# base_board4.net
KiCad netlist of a schematic drawn in EAGLE
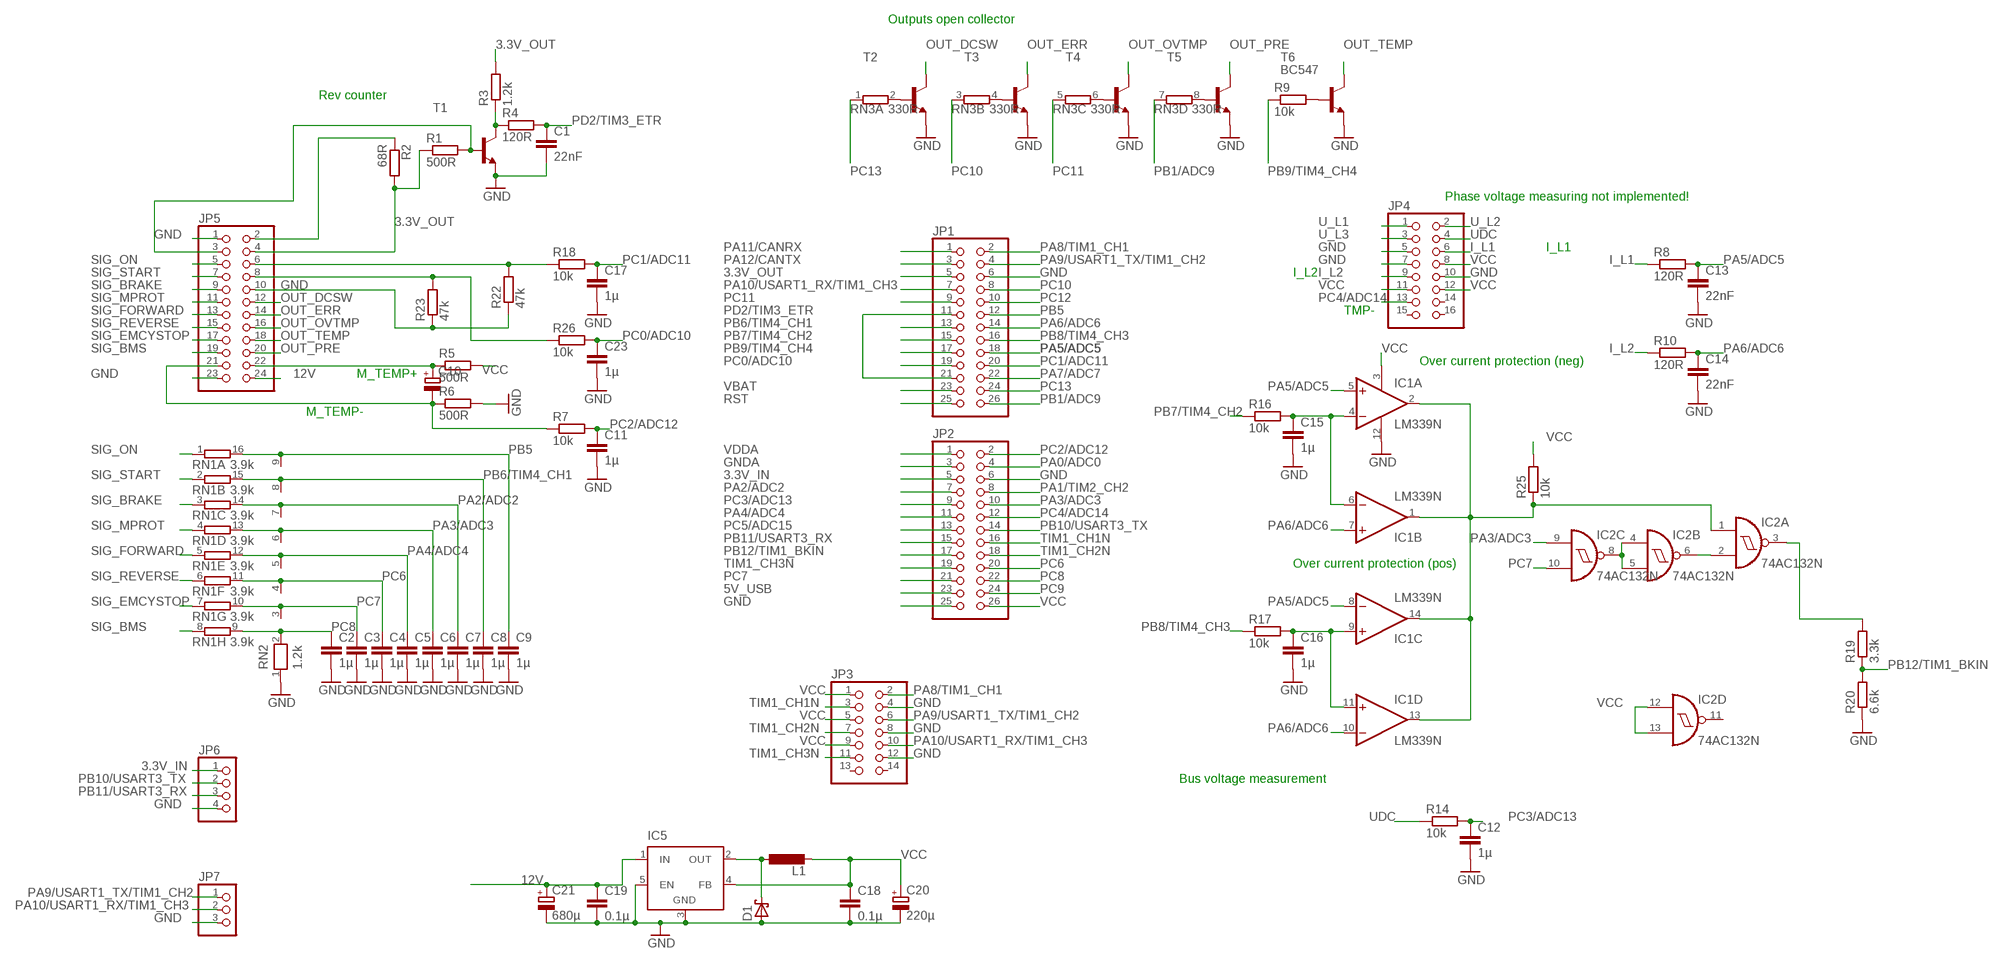
[diagram p0: schematic, sheet 1]

(export (version "E")
  (design (tool "Eeschema 10.0.6"))
  (components
    (comp (ref "C1")
      (value "22nF")
      (footprint "eagle-import:C025-024X044")
      (libsource (lib "eagle-import") (part "C-EU025-024X044"))
    )
    (comp (ref "C2")
      (value "1µ")
      (footprint "eagle-import:C025-024X044")
      (libsource (lib "eagle-import") (part "C-EU025-024X044"))
    )
    (comp (ref "C3")
      (value "1µ")
      (footprint "eagle-import:C025-024X044")
      (libsource (lib "eagle-import") (part "C-EU025-024X044"))
    )
    (comp (ref "C4")
      (value "1µ")
      (footprint "eagle-import:C025-024X044")
      (libsource (lib "eagle-import") (part "C-EU025-024X044"))
    )
    (comp (ref "C5")
      (value "1µ")
      (footprint "eagle-import:C025-024X044")
      (libsource (lib "eagle-import") (part "C-EU025-024X044"))
    )
    (comp (ref "C6")
      (value "1µ")
      (footprint "eagle-import:C025-024X044")
      (libsource (lib "eagle-import") (part "C-EU025-024X044"))
    )
    (comp (ref "C7")
      (value "1µ")
      (footprint "eagle-import:C025-024X044")
      (libsource (lib "eagle-import") (part "C-EU025-024X044"))
    )
    (comp (ref "C8")
      (value "1µ")
      (footprint "eagle-import:C025-024X044")
      (libsource (lib "eagle-import") (part "C-EU025-024X044"))
    )
    (comp (ref "C9")
      (value "1µ")
      (footprint "eagle-import:C025-024X044")
      (libsource (lib "eagle-import") (part "C-EU025-024X044"))
    )
    (comp (ref "C10")
      (value "CPOL-EUE2-4")
      (footprint "eagle-import:E2-4")
      (libsource (lib "eagle-import") (part "CPOL-EUE2-4"))
    )
    (comp (ref "C11")
      (value "1µ")
      (footprint "eagle-import:C025-024X044")
      (libsource (lib "eagle-import") (part "C-EU025-024X044"))
    )
    (comp (ref "C12")
      (value "1µ")
      (footprint "eagle-import:C025-024X044")
      (libsource (lib "eagle-import") (part "C-EU025-024X044"))
    )
    (comp (ref "C13")
      (value "22nF")
      (footprint "eagle-import:C025-024X044")
      (libsource (lib "eagle-import") (part "C-EU025-024X044"))
    )
    (comp (ref "C14")
      (value "22nF")
      (footprint "eagle-import:C025-024X044")
      (libsource (lib "eagle-import") (part "C-EU025-024X044"))
    )
    (comp (ref "C15")
      (value "1µ")
      (footprint "eagle-import:C025-024X044")
      (libsource (lib "eagle-import") (part "C-EU025-024X044"))
    )
    (comp (ref "C16")
      (value "1µ")
      (footprint "eagle-import:C025-024X044")
      (libsource (lib "eagle-import") (part "C-EU025-024X044"))
    )
    (comp (ref "C17")
      (value "1µ")
      (footprint "eagle-import:C025-024X044")
      (libsource (lib "eagle-import") (part "C-EU025-024X044"))
    )
    (comp (ref "C18")
      (value "0.1µ")
      (footprint "eagle-import:C050-024X044")
      (libsource (lib "eagle-import") (part "C-EU050-024X044"))
    )
    (comp (ref "C19")
      (value "0.1µ")
      (footprint "eagle-import:C050-024X044")
      (libsource (lib "eagle-import") (part "C-EU050-024X044"))
    )
    (comp (ref "C20")
      (value "220µ")
      (footprint "eagle-import:E2-4")
      (libsource (lib "eagle-import") (part "CPOL-EUE2-4"))
    )
    (comp (ref "C21")
      (value "680µ")
      (footprint "eagle-import:E2,5-5")
      (libsource (lib "eagle-import") (part "CPOL-EUE2.5-5"))
    )
    (comp (ref "C23")
      (value "1µ")
      (footprint "eagle-import:C025-024X044")
      (libsource (lib "eagle-import") (part "C-EU025-024X044"))
    )
    (comp (ref "D1")
      (value "SCHOTTKY-DIODEDO201T15")
      (footprint "eagle-import:DO201T15")
      (libsource (lib "eagle-import") (part "SCHOTTKY-DIODEDO201T15"))
    )
    (comp (ref "IC1")
      (value "LM339N")
      (footprint "eagle-import:DIL14")
      (libsource (lib "eagle-import") (part "LM339N"))
    )
    (comp (ref "IC2")
      (value "74AC132N")
      (footprint "eagle-import:DIL14")
      (libsource (lib "eagle-import") (part "74132NAC"))
    )
    (comp (ref "IC5")
      (value "LM2596TV")
      (footprint "eagle-import:TO220-51")
      (libsource (lib "eagle-import") (part "LM2596TV"))
    )
    (comp (ref "JP1")
      (value "PINHD-2X13")
      (footprint "eagle-import:2X13")
      (libsource (lib "eagle-import") (part "PINHD-2X13"))
    )
    (comp (ref "JP2")
      (value "PINHD-2X13")
      (footprint "eagle-import:2X13")
      (libsource (lib "eagle-import") (part "PINHD-2X13"))
    )
    (comp (ref "JP3")
      (value "PINHD-2X7")
      (footprint "eagle-import:2X07")
      (libsource (lib "eagle-import") (part "PINHD-2X7"))
    )
    (comp (ref "JP4")
      (value "PINHD-2X8")
      (footprint "eagle-import:2X08")
      (libsource (lib "eagle-import") (part "PINHD-2X8"))
    )
    (comp (ref "JP5")
      (value "PINHD-2X12")
      (footprint "eagle-import:2X12")
      (libsource (lib "eagle-import") (part "PINHD-2X12"))
    )
    (comp (ref "JP6")
      (value "PINHD-1X4")
      (footprint "eagle-import:1X04")
      (libsource (lib "eagle-import") (part "PINHD-1X4"))
    )
    (comp (ref "JP7")
      (value "PINHD-1X3")
      (footprint "eagle-import:1X03")
      (libsource (lib "eagle-import") (part "PINHD-1X3"))
    )
    (comp (ref "L1")
      (value "L-EUTJ3-U1")
      (footprint "eagle-import:TJ3-U1")
      (libsource (lib "eagle-import") (part "L-EUTJ3-U1"))
    )
    (comp (ref "R1")
      (value "500R")
      (footprint "eagle-import:0207_10")
      (libsource (lib "eagle-import") (part "R-EU_0207/10"))
    )
    (comp (ref "R2")
      (value "68R")
      (footprint "eagle-import:0207_10")
      (libsource (lib "eagle-import") (part "R-EU_0207/10"))
    )
    (comp (ref "R3")
      (value "1.2k")
      (footprint "eagle-import:0207_10")
      (libsource (lib "eagle-import") (part "R-EU_0207/10"))
    )
    (comp (ref "R4")
      (value "120R")
      (footprint "eagle-import:0207_10")
      (libsource (lib "eagle-import") (part "R-EU_0207/10"))
    )
    (comp (ref "R5")
      (value "500R")
      (footprint "eagle-import:0207_10")
      (libsource (lib "eagle-import") (part "R-EU_0207/10"))
    )
    (comp (ref "R6")
      (value "500R")
      (footprint "eagle-import:0207_10")
      (libsource (lib "eagle-import") (part "R-EU_0207/10"))
    )
    (comp (ref "R7")
      (value "10k")
      (footprint "eagle-import:0207_10")
      (libsource (lib "eagle-import") (part "R-EU_0207/10"))
    )
    (comp (ref "R8")
      (value "120R")
      (footprint "eagle-import:0207_10")
      (libsource (lib "eagle-import") (part "R-EU_0207/10"))
    )
    (comp (ref "R9")
      (value "10k")
      (footprint "eagle-import:0207_10")
      (libsource (lib "eagle-import") (part "R-EU_0207/10"))
    )
    (comp (ref "R10")
      (value "120R")
      (footprint "eagle-import:0207_10")
      (libsource (lib "eagle-import") (part "R-EU_0207/10"))
    )
    (comp (ref "R14")
      (value "10k")
      (footprint "eagle-import:0207_10")
      (libsource (lib "eagle-import") (part "R-EU_0207/10"))
    )
    (comp (ref "R16")
      (value "10k")
      (footprint "eagle-import:0207_10")
      (libsource (lib "eagle-import") (part "R-EU_0207/10"))
    )
    (comp (ref "R17")
      (value "10k")
      (footprint "eagle-import:0207_10")
      (libsource (lib "eagle-import") (part "R-EU_0207/10"))
    )
    (comp (ref "R18")
      (value "10k")
      (footprint "eagle-import:0207_10")
      (libsource (lib "eagle-import") (part "R-EU_0207/10"))
    )
    (comp (ref "R19")
      (value "3.3k")
      (footprint "eagle-import:0207_10")
      (libsource (lib "eagle-import") (part "R-EU_0207/10"))
    )
    (comp (ref "R20")
      (value "6.6k")
      (footprint "eagle-import:0207_10")
      (libsource (lib "eagle-import") (part "R-EU_0207/10"))
    )
    (comp (ref "R22")
      (value "47k")
      (footprint "eagle-import:0207_10")
      (libsource (lib "eagle-import") (part "R-EU_0207/10"))
    )
    (comp (ref "R23")
      (value "47k")
      (footprint "eagle-import:0207_10")
      (libsource (lib "eagle-import") (part "R-EU_0207/10"))
    )
    (comp (ref "R25")
      (value "10k")
      (footprint "eagle-import:0207_10")
      (libsource (lib "eagle-import") (part "R-EU_0207/10"))
    )
    (comp (ref "R26")
      (value "10k")
      (footprint "eagle-import:0207_10")
      (libsource (lib "eagle-import") (part "R-EU_0207/10"))
    )
    (comp (ref "RN1")
      (value "3.9k")
      (footprint "eagle-import:DIL16")
      (libsource (lib "eagle-import") (part "8R-N"))
    )
    (comp (ref "RN2")
      (value "1.2k")
      (footprint "eagle-import:RN-9")
      (libsource (lib "eagle-import") (part "RN08"))
    )
    (comp (ref "RN3")
      (value "330R")
      (footprint "eagle-import:SIL8")
      (libsource (lib "eagle-import") (part "E4R"))
    )
    (comp (ref "T1")
      (value "BC547B-NPN-TO92-EBC")
      (footprint "eagle-import:TO92-EBC")
      (libsource (lib "eagle-import") (part "-NPN-TO92-EBCBC547B"))
    )
    (comp (ref "T2")
      (value "-NPN-TO92-EBC")
      (footprint "eagle-import:TO92-EBC")
      (libsource (lib "eagle-import") (part "transistor-neu-to92_-NPN-TO92-EBC"))
    )
    (comp (ref "T3")
      (value "-NPN-TO92-EBC")
      (footprint "eagle-import:TO92-EBC")
      (libsource (lib "eagle-import") (part "transistor-neu-to92_-NPN-TO92-EBC"))
    )
    (comp (ref "T4")
      (value "-NPN-TO92-EBC")
      (footprint "eagle-import:TO92-EBC")
      (libsource (lib "eagle-import") (part "transistor-neu-to92_-NPN-TO92-EBC"))
    )
    (comp (ref "T5")
      (value "-NPN-TO92-EBC")
      (footprint "eagle-import:TO92-EBC")
      (libsource (lib "eagle-import") (part "transistor-neu-to92_-NPN-TO92-EBC"))
    )
    (comp (ref "T6")
      (value "BC547")
      (footprint "eagle-import:TO92")
      (libsource (lib "eagle-import") (part "BC547"))
    )
  )
  (nets
    (net (code "1") (name "/3.3V_IN") (class "Default")
      (node (ref "JP2") (pin "5") (pinfunction "5_5") (pintype "passive"))
      (node (ref "JP6") (pin "1") (pinfunction "1_1") (pintype "passive"))
    )
    (net (code "2") (name "/3.3V_OUT") (class "Default")
      (node (ref "JP1") (pin "5") (pinfunction "5_5") (pintype "passive"))
      (node (ref "JP5") (pin "4") (pinfunction "4_4") (pintype "passive"))
      (node (ref "R1") (pin "1") (pinfunction "1_1") (pintype "passive"))
      (node (ref "R2") (pin "2") (pinfunction "2_2") (pintype "passive"))
      (node (ref "R3") (pin "2") (pinfunction "2_2") (pintype "passive"))
    )
    (net (code "3") (name "/5V_USB") (class "Default")
      (node (ref "JP2") (pin "23") (pinfunction "23_23") (pintype "passive"))
    )
    (net (code "4") (name "/12V") (class "Default")
      (node (ref "C19") (pin "1") (pinfunction "1_1") (pintype "passive"))
      (node (ref "C21") (pin "+") (pinfunction "+_+") (pintype "passive"))
      (node (ref "IC5") (pin "1") (pinfunction "IN_1") (pintype "input"))
      (node (ref "JP5") (pin "24") (pinfunction "24_24") (pintype "passive"))
    )
    (net (code "5") (name "/GNDA") (class "Default")
      (node (ref "JP2") (pin "3") (pinfunction "3_3") (pintype "passive"))
    )
    (net (code "6") (name "/I_L1") (class "Default")
      (node (ref "JP4") (pin "6") (pinfunction "6_6") (pintype "passive"))
      (node (ref "R8") (pin "1") (pinfunction "1_1") (pintype "passive"))
    )
    (net (code "7") (name "/I_L2") (class "Default")
      (node (ref "JP4") (pin "9") (pinfunction "9_9") (pintype "passive"))
      (node (ref "R10") (pin "1") (pinfunction "1_1") (pintype "passive"))
    )
    (net (code "8") (name "/OUT_DCSW") (class "Default")
      (node (ref "JP5") (pin "12") (pinfunction "12_12") (pintype "passive"))
      (node (ref "T2") (pin "C") (pinfunction "C_C") (pintype "passive"))
    )
    (net (code "9") (name "/OUT_ERR") (class "Default")
      (node (ref "JP5") (pin "14") (pinfunction "14_14") (pintype "passive"))
      (node (ref "T3") (pin "C") (pinfunction "C_C") (pintype "passive"))
    )
    (net (code "10") (name "/OUT_OVTMP") (class "Default")
      (node (ref "JP5") (pin "16") (pinfunction "16_16") (pintype "passive"))
      (node (ref "T4") (pin "C") (pinfunction "C_C") (pintype "passive"))
    )
    (net (code "11") (name "/OUT_PRE") (class "Default")
      (node (ref "JP5") (pin "20") (pinfunction "20_20") (pintype "passive"))
      (node (ref "T5") (pin "C") (pinfunction "C_C") (pintype "passive"))
    )
    (net (code "12") (name "/OUT_TEMP") (class "Default")
      (node (ref "JP5") (pin "18") (pinfunction "18_18") (pintype "passive"))
      (node (ref "T6") (pin "3") (pinfunction "C_3") (pintype "passive"))
    )
    (net (code "13") (name "/PA0{slash}ADC0") (class "Default")
      (node (ref "JP2") (pin "4") (pinfunction "4_4") (pintype "passive"))
    )
    (net (code "14") (name "/PA1{slash}TIM2_CH2") (class "Default")
      (node (ref "JP2") (pin "8") (pinfunction "8_8") (pintype "passive"))
    )
    (net (code "15") (name "/PA2{slash}ADC2") (class "Default")
      (node (ref "C7") (pin "1") (pinfunction "1_1") (pintype "passive"))
      (node (ref "JP2") (pin "7") (pinfunction "7_7") (pintype "passive"))
      (node (ref "RN1") (pin "14") (pinfunction "2_14") (pintype "passive"))
      (node (ref "RN2") (pin "7") (pinfunction "7_7") (pintype "passive"))
    )
    (net (code "16") (name "/PA3{slash}ADC3") (class "Default")
      (node (ref "C6") (pin "1") (pinfunction "1_1") (pintype "passive"))
      (node (ref "IC2") (pin "9") (pinfunction "I0_9") (pintype "input"))
      (node (ref "JP2") (pin "10") (pinfunction "10_10") (pintype "passive"))
      (node (ref "RN1") (pin "13") (pinfunction "2_13") (pintype "passive"))
      (node (ref "RN2") (pin "6") (pinfunction "6_6") (pintype "passive"))
    )
    (net (code "17") (name "/PA4{slash}ADC4") (class "Default")
      (node (ref "C5") (pin "1") (pinfunction "1_1") (pintype "passive"))
      (node (ref "JP2") (pin "11") (pinfunction "11_11") (pintype "passive"))
      (node (ref "RN1") (pin "12") (pinfunction "2_12") (pintype "passive"))
      (node (ref "RN2") (pin "5") (pinfunction "5_5") (pintype "passive"))
    )
    (net (code "18") (name "/PA5{slash}ADC5") (class "Default")
      (node (ref "C13") (pin "1") (pinfunction "1_1") (pintype "passive"))
      (node (ref "IC1") (pin "5") (pinfunction "+IN_5") (pintype "input"))
      (node (ref "IC1") (pin "8") (pinfunction "-IN_8") (pintype "input"))
      (node (ref "JP1") (pin "18") (pinfunction "18_18") (pintype "passive"))
      (node (ref "R8") (pin "2") (pinfunction "2_2") (pintype "passive"))
    )
    (net (code "19") (name "/PA6{slash}ADC6") (class "Default")
      (node (ref "C14") (pin "1") (pinfunction "1_1") (pintype "passive"))
      (node (ref "IC1") (pin "10") (pinfunction "-IN_10") (pintype "input"))
      (node (ref "IC1") (pin "7") (pinfunction "+IN_7") (pintype "input"))
      (node (ref "JP1") (pin "14") (pinfunction "14_14") (pintype "passive"))
      (node (ref "R10") (pin "2") (pinfunction "2_2") (pintype "passive"))
    )
    (net (code "20") (name "/PA7{slash}ADC7") (class "Default")
      (node (ref "JP1") (pin "22") (pinfunction "22_22") (pintype "passive"))
    )
    (net (code "21") (name "/PA8{slash}TIM1_CH1") (class "Default")
      (node (ref "JP1") (pin "2") (pinfunction "2_2") (pintype "passive"))
      (node (ref "JP3") (pin "2") (pinfunction "2_2") (pintype "passive"))
    )
    (net (code "22") (name "/PA9{slash}USART1_TX{slash}TIM1_CH2") (class "Default")
      (node (ref "JP1") (pin "4") (pinfunction "4_4") (pintype "passive"))
      (node (ref "JP3") (pin "6") (pinfunction "6_6") (pintype "passive"))
      (node (ref "JP7") (pin "1") (pinfunction "1_1") (pintype "passive"))
    )
    (net (code "23") (name "/PA10{slash}USART1_RX{slash}TIM1_CH3") (class "Default")
      (node (ref "JP1") (pin "7") (pinfunction "7_7") (pintype "passive"))
      (node (ref "JP3") (pin "10") (pinfunction "10_10") (pintype "passive"))
      (node (ref "JP7") (pin "2") (pinfunction "2_2") (pintype "passive"))
    )
    (net (code "24") (name "/PA11{slash}CANRX") (class "Default")
      (node (ref "JP1") (pin "1") (pinfunction "1_1") (pintype "passive"))
    )
    (net (code "25") (name "/PA12{slash}CANTX") (class "Default")
      (node (ref "JP1") (pin "3") (pinfunction "3_3") (pintype "passive"))
    )
    (net (code "26") (name "/PB1{slash}ADC9") (class "Default")
      (node (ref "JP1") (pin "26") (pinfunction "26_26") (pintype "passive"))
      (node (ref "RN3") (pin "7") (pinfunction "1_7") (pintype "passive"))
    )
    (net (code "27") (name "/PB5") (class "Default")
      (node (ref "C9") (pin "1") (pinfunction "1_1") (pintype "passive"))
      (node (ref "JP1") (pin "12") (pinfunction "12_12") (pintype "passive"))
      (node (ref "RN1") (pin "16") (pinfunction "2_16") (pintype "passive"))
      (node (ref "RN2") (pin "9") (pinfunction "9_9") (pintype "passive"))
    )
    (net (code "28") (name "/PB6{slash}TIM4_CH1") (class "Default")
      (node (ref "C8") (pin "1") (pinfunction "1_1") (pintype "passive"))
      (node (ref "JP1") (pin "13") (pinfunction "13_13") (pintype "passive"))
      (node (ref "RN1") (pin "15") (pinfunction "2_15") (pintype "passive"))
      (node (ref "RN2") (pin "8") (pinfunction "8_8") (pintype "passive"))
    )
    (net (code "29") (name "/PB7{slash}TIM4_CH2") (class "Default")
      (node (ref "JP1") (pin "15") (pinfunction "15_15") (pintype "passive"))
      (node (ref "R16") (pin "1") (pinfunction "1_1") (pintype "passive"))
    )
    (net (code "30") (name "/PB8{slash}TIM4_CH3") (class "Default")
      (node (ref "JP1") (pin "16") (pinfunction "16_16") (pintype "passive"))
      (node (ref "R17") (pin "1") (pinfunction "1_1") (pintype "passive"))
    )
    (net (code "31") (name "/PB9{slash}TIM4_CH4") (class "Default")
      (node (ref "JP1") (pin "17") (pinfunction "17_17") (pintype "passive"))
      (node (ref "R9") (pin "1") (pinfunction "1_1") (pintype "passive"))
    )
    (net (code "32") (name "/PB10{slash}USART3_TX") (class "Default")
      (node (ref "JP2") (pin "14") (pinfunction "14_14") (pintype "passive"))
      (node (ref "JP6") (pin "2") (pinfunction "2_2") (pintype "passive"))
    )
    (net (code "33") (name "/PB11{slash}USART3_RX") (class "Default")
      (node (ref "JP2") (pin "15") (pinfunction "15_15") (pintype "passive"))
      (node (ref "JP6") (pin "3") (pinfunction "3_3") (pintype "passive"))
    )
    (net (code "34") (name "/PB12{slash}TIM1_BKIN") (class "Default")
      (node (ref "JP2") (pin "17") (pinfunction "17_17") (pintype "passive"))
      (node (ref "R19") (pin "1") (pinfunction "1_1") (pintype "passive"))
      (node (ref "R20") (pin "2") (pinfunction "2_2") (pintype "passive"))
    )
    (net (code "35") (name "/PC0{slash}ADC10") (class "Default")
      (node (ref "C23") (pin "1") (pinfunction "1_1") (pintype "passive"))
      (node (ref "JP1") (pin "19") (pinfunction "19_19") (pintype "passive"))
      (node (ref "R26") (pin "2") (pinfunction "2_2") (pintype "passive"))
    )
    (net (code "36") (name "/PC1{slash}ADC11") (class "Default")
      (node (ref "C17") (pin "1") (pinfunction "1_1") (pintype "passive"))
      (node (ref "JP1") (pin "20") (pinfunction "20_20") (pintype "passive"))
      (node (ref "R18") (pin "2") (pinfunction "2_2") (pintype "passive"))
    )
    (net (code "37") (name "/PC2{slash}ADC12") (class "Default")
      (node (ref "C11") (pin "1") (pinfunction "1_1") (pintype "passive"))
      (node (ref "JP2") (pin "2") (pinfunction "2_2") (pintype "passive"))
      (node (ref "R7") (pin "2") (pinfunction "2_2") (pintype "passive"))
    )
    (net (code "38") (name "/PC3{slash}ADC13") (class "Default")
      (node (ref "C12") (pin "1") (pinfunction "1_1") (pintype "passive"))
      (node (ref "JP2") (pin "9") (pinfunction "9_9") (pintype "passive"))
      (node (ref "R14") (pin "2") (pinfunction "2_2") (pintype "passive"))
    )
    (net (code "39") (name "/PC4{slash}ADC14") (class "Default")
      (node (ref "JP2") (pin "12") (pinfunction "12_12") (pintype "passive"))
      (node (ref "JP4") (pin "13") (pinfunction "13_13") (pintype "passive"))
    )
    (net (code "40") (name "/PC5{slash}ADC15") (class "Default")
      (node (ref "JP2") (pin "13") (pinfunction "13_13") (pintype "passive"))
    )
    (net (code "41") (name "/PC6") (class "Default")
      (node (ref "C4") (pin "1") (pinfunction "1_1") (pintype "passive"))
      (node (ref "JP2") (pin "20") (pinfunction "20_20") (pintype "passive"))
      (node (ref "RN1") (pin "11") (pinfunction "2_11") (pintype "passive"))
      (node (ref "RN2") (pin "4") (pinfunction "4_4") (pintype "passive"))
    )
    (net (code "42") (name "/PC7") (class "Default")
      (node (ref "C3") (pin "1") (pinfunction "1_1") (pintype "passive"))
      (node (ref "IC2") (pin "10") (pinfunction "I1_10") (pintype "input"))
      (node (ref "JP2") (pin "21") (pinfunction "21_21") (pintype "passive"))
      (node (ref "RN1") (pin "10") (pinfunction "2_10") (pintype "passive"))
      (node (ref "RN2") (pin "3") (pinfunction "3_3") (pintype "passive"))
    )
    (net (code "43") (name "/PC8") (class "Default")
      (node (ref "C2") (pin "1") (pinfunction "1_1") (pintype "passive"))
      (node (ref "JP2") (pin "22") (pinfunction "22_22") (pintype "passive"))
      (node (ref "RN1") (pin "9") (pinfunction "2_9") (pintype "passive"))
      (node (ref "RN2") (pin "2") (pinfunction "2_2") (pintype "passive"))
    )
    (net (code "44") (name "/PC9") (class "Default")
      (node (ref "JP2") (pin "24") (pinfunction "24_24") (pintype "passive"))
    )
    (net (code "45") (name "/PC10") (class "Default")
      (node (ref "JP1") (pin "8") (pinfunction "8_8") (pintype "passive"))
      (node (ref "RN3") (pin "3") (pinfunction "1_3") (pintype "passive"))
    )
    (net (code "46") (name "/PC11") (class "Default")
      (node (ref "JP1") (pin "9") (pinfunction "9_9") (pintype "passive"))
      (node (ref "RN3") (pin "5") (pinfunction "1_5") (pintype "passive"))
    )
    (net (code "47") (name "/PC12") (class "Default")
      (node (ref "JP1") (pin "10") (pinfunction "10_10") (pintype "passive"))
    )
    (net (code "48") (name "/PC13") (class "Default")
      (node (ref "JP1") (pin "24") (pinfunction "24_24") (pintype "passive"))
      (node (ref "RN3") (pin "1") (pinfunction "1_1") (pintype "passive"))
    )
    (net (code "49") (name "/PD2{slash}TIM3_ETR") (class "Default")
      (node (ref "C1") (pin "1") (pinfunction "1_1") (pintype "passive"))
      (node (ref "JP1") (pin "11") (pinfunction "11_11") (pintype "passive"))
      (node (ref "JP1") (pin "21") (pinfunction "21_21") (pintype "passive"))
      (node (ref "R4") (pin "2") (pinfunction "2_2") (pintype "passive"))
    )
    (net (code "50") (name "/RST") (class "Default")
      (node (ref "JP1") (pin "25") (pinfunction "25_25") (pintype "passive"))
    )
    (net (code "51") (name "/SIG_BMS") (class "Default")
      (node (ref "JP5") (pin "19") (pinfunction "19_19") (pintype "passive"))
      (node (ref "RN1") (pin "8") (pinfunction "1_8") (pintype "passive"))
    )
    (net (code "52") (name "/SIG_BRAKE") (class "Default")
      (node (ref "JP5") (pin "9") (pinfunction "9_9") (pintype "passive"))
      (node (ref "RN1") (pin "3") (pinfunction "1_3") (pintype "passive"))
    )
    (net (code "53") (name "/SIG_EMCYSTOP") (class "Default")
      (node (ref "JP5") (pin "17") (pinfunction "17_17") (pintype "passive"))
      (node (ref "RN1") (pin "7") (pinfunction "1_7") (pintype "passive"))
    )
    (net (code "54") (name "/SIG_FORWARD") (class "Default")
      (node (ref "JP5") (pin "13") (pinfunction "13_13") (pintype "passive"))
      (node (ref "RN1") (pin "5") (pinfunction "1_5") (pintype "passive"))
    )
    (net (code "55") (name "/SIG_MPROT") (class "Default")
      (node (ref "JP5") (pin "11") (pinfunction "11_11") (pintype "passive"))
      (node (ref "RN1") (pin "4") (pinfunction "1_4") (pintype "passive"))
    )
    (net (code "56") (name "/SIG_ON") (class "Default")
      (node (ref "JP5") (pin "5") (pinfunction "5_5") (pintype "passive"))
      (node (ref "RN1") (pin "1") (pinfunction "1_1") (pintype "passive"))
    )
    (net (code "57") (name "/SIG_REVERSE") (class "Default")
      (node (ref "JP5") (pin "15") (pinfunction "15_15") (pintype "passive"))
      (node (ref "RN1") (pin "6") (pinfunction "1_6") (pintype "passive"))
    )
    (net (code "58") (name "/SIG_START") (class "Default")
      (node (ref "JP5") (pin "7") (pinfunction "7_7") (pintype "passive"))
      (node (ref "RN1") (pin "2") (pinfunction "1_2") (pintype "passive"))
    )
    (net (code "59") (name "/TIM1_CH1N") (class "Default")
      (node (ref "JP2") (pin "16") (pinfunction "16_16") (pintype "passive"))
      (node (ref "JP3") (pin "3") (pinfunction "3_3") (pintype "passive"))
    )
    (net (code "60") (name "/TIM1_CH2N") (class "Default")
      (node (ref "JP2") (pin "18") (pinfunction "18_18") (pintype "passive"))
      (node (ref "JP3") (pin "7") (pinfunction "7_7") (pintype "passive"))
    )
    (net (code "61") (name "/TIM1_CH3N") (class "Default")
      (node (ref "JP2") (pin "19") (pinfunction "19_19") (pintype "passive"))
      (node (ref "JP3") (pin "11") (pinfunction "11_11") (pintype "passive"))
    )
    (net (code "62") (name "/UDC") (class "Default")
      (node (ref "JP4") (pin "4") (pinfunction "4_4") (pintype "passive"))
      (node (ref "R14") (pin "1") (pinfunction "1_1") (pintype "passive"))
    )
    (net (code "63") (name "/U_L1") (class "Default")
      (node (ref "JP4") (pin "1") (pinfunction "1_1") (pintype "passive"))
    )
    (net (code "64") (name "/U_L2") (class "Default")
      (node (ref "JP4") (pin "2") (pinfunction "2_2") (pintype "passive"))
    )
    (net (code "65") (name "/U_L3") (class "Default")
      (node (ref "JP4") (pin "3") (pinfunction "3_3") (pintype "passive"))
    )
    (net (code "66") (name "/VBAT") (class "Default")
      (node (ref "JP1") (pin "23") (pinfunction "23_23") (pintype "passive"))
    )
    (net (code "67") (name "/VCC") (class "Default")
      (node (ref "C18") (pin "1") (pinfunction "1_1") (pintype "passive"))
      (node (ref "C20") (pin "+") (pinfunction "+_+") (pintype "passive"))
      (node (ref "IC1") (pin "3") (pinfunction "V+_3") (pintype "power_in"))
      (node (ref "IC2") (pin "12") (pinfunction "I0_12") (pintype "input"))
      (node (ref "IC2") (pin "13") (pinfunction "I1_13") (pintype "input"))
      (node (ref "IC5") (pin "4") (pinfunction "FB_4") (pintype "input"))
      (node (ref "JP2") (pin "26") (pinfunction "26_26") (pintype "passive"))
      (node (ref "JP3") (pin "1") (pinfunction "1_1") (pintype "passive"))
      (node (ref "JP3") (pin "5") (pinfunction "5_5") (pintype "passive"))
      (node (ref "JP3") (pin "9") (pinfunction "9_9") (pintype "passive"))
      (node (ref "JP4") (pin "11") (pinfunction "11_11") (pintype "passive"))
      (node (ref "JP4") (pin "12") (pinfunction "12_12") (pintype "passive"))
      (node (ref "JP4") (pin "8") (pinfunction "8_8") (pintype "passive"))
      (node (ref "L1") (pin "2") (pinfunction "2_2") (pintype "passive"))
      (node (ref "R25") (pin "2") (pinfunction "2_2") (pintype "passive"))
      (node (ref "R5") (pin "2") (pinfunction "2_2") (pintype "passive"))
    )
    (net (code "68") (name "/VDDA") (class "Default")
      (node (ref "JP2") (pin "1") (pinfunction "1_1") (pintype "passive"))
    )
    (net (code "69") (name "GND") (class "Default")
      (node (ref "C1") (pin "2") (pinfunction "2_2") (pintype "passive"))
      (node (ref "C11") (pin "2") (pinfunction "2_2") (pintype "passive"))
      (node (ref "C12") (pin "2") (pinfunction "2_2") (pintype "passive"))
      (node (ref "C13") (pin "2") (pinfunction "2_2") (pintype "passive"))
      (node (ref "C14") (pin "2") (pinfunction "2_2") (pintype "passive"))
      (node (ref "C15") (pin "2") (pinfunction "2_2") (pintype "passive"))
      (node (ref "C16") (pin "2") (pinfunction "2_2") (pintype "passive"))
      (node (ref "C17") (pin "2") (pinfunction "2_2") (pintype "passive"))
      (node (ref "C18") (pin "2") (pinfunction "2_2") (pintype "passive"))
      (node (ref "C19") (pin "2") (pinfunction "2_2") (pintype "passive"))
      (node (ref "C2") (pin "2") (pinfunction "2_2") (pintype "passive"))
      (node (ref "C20") (pin "-") (pinfunction "-_-") (pintype "passive"))
      (node (ref "C21") (pin "-") (pinfunction "-_-") (pintype "passive"))
      (node (ref "C23") (pin "2") (pinfunction "2_2") (pintype "passive"))
      (node (ref "C3") (pin "2") (pinfunction "2_2") (pintype "passive"))
      (node (ref "C4") (pin "2") (pinfunction "2_2") (pintype "passive"))
      (node (ref "C5") (pin "2") (pinfunction "2_2") (pintype "passive"))
      (node (ref "C6") (pin "2") (pinfunction "2_2") (pintype "passive"))
      (node (ref "C7") (pin "2") (pinfunction "2_2") (pintype "passive"))
      (node (ref "C8") (pin "2") (pinfunction "2_2") (pintype "passive"))
      (node (ref "C9") (pin "2") (pinfunction "2_2") (pintype "passive"))
      (node (ref "D1") (pin "A") (pinfunction "A_A") (pintype "passive"))
      (node (ref "IC1") (pin "12") (pinfunction "GND_12") (pintype "power_in"))
      (node (ref "IC5") (pin "3") (pinfunction "GND_3") (pintype "power_in"))
      (node (ref "IC5") (pin "5") (pinfunction "EN_5") (pintype "input"))
      (node (ref "JP1") (pin "6") (pinfunction "6_6") (pintype "passive"))
      (node (ref "JP2") (pin "25") (pinfunction "25_25") (pintype "passive"))
      (node (ref "JP2") (pin "6") (pinfunction "6_6") (pintype "passive"))
      (node (ref "JP3") (pin "12") (pinfunction "12_12") (pintype "passive"))
      (node (ref "JP3") (pin "4") (pinfunction "4_4") (pintype "passive"))
      (node (ref "JP3") (pin "8") (pinfunction "8_8") (pintype "passive"))
      (node (ref "JP4") (pin "10") (pinfunction "10_10") (pintype "passive"))
      (node (ref "JP4") (pin "5") (pinfunction "5_5") (pintype "passive"))
      (node (ref "JP4") (pin "7") (pinfunction "7_7") (pintype "passive"))
      (node (ref "JP5") (pin "1") (pinfunction "1_1") (pintype "passive"))
      (node (ref "JP5") (pin "10") (pinfunction "10_10") (pintype "passive"))
      (node (ref "JP5") (pin "23") (pinfunction "23_23") (pintype "passive"))
      (node (ref "JP6") (pin "4") (pinfunction "4_4") (pintype "passive"))
      (node (ref "JP7") (pin "3") (pinfunction "3_3") (pintype "passive"))
      (node (ref "R20") (pin "1") (pinfunction "1_1") (pintype "passive"))
      (node (ref "R22") (pin "1") (pinfunction "1_1") (pintype "passive"))
      (node (ref "R23") (pin "1") (pinfunction "1_1") (pintype "passive"))
      (node (ref "R6") (pin "2") (pinfunction "2_2") (pintype "passive"))
      (node (ref "RN2") (pin "1") (pinfunction "1_1") (pintype "passive"))
      (node (ref "T1") (pin "E") (pinfunction "E_E") (pintype "passive"))
      (node (ref "T2") (pin "E") (pinfunction "E_E") (pintype "passive"))
      (node (ref "T3") (pin "E") (pinfunction "E_E") (pintype "passive"))
      (node (ref "T4") (pin "E") (pinfunction "E_E") (pintype "passive"))
      (node (ref "T5") (pin "E") (pinfunction "E_E") (pintype "passive"))
      (node (ref "T6") (pin "1") (pinfunction "E_1") (pintype "passive"))
    )
    (net (code "70") (name "Net-(C10-Pad+)") (class "Default")
      (node (ref "C10") (pin "+") (pinfunction "+_+") (pintype "passive"))
      (node (ref "JP5") (pin "22") (pinfunction "22_22") (pintype "passive"))
      (node (ref "R5") (pin "1") (pinfunction "1_1") (pintype "passive"))
    )
    (net (code "71") (name "Net-(C10-Pad-)") (class "Default")
      (node (ref "C10") (pin "-") (pinfunction "-_-") (pintype "passive"))
      (node (ref "JP5") (pin "21") (pinfunction "21_21") (pintype "passive"))
      (node (ref "R6") (pin "1") (pinfunction "1_1") (pintype "passive"))
      (node (ref "R7") (pin "1") (pinfunction "1_1") (pintype "passive"))
    )
    (net (code "72") (name "Net-(IC1A--IN)") (class "Default")
      (node (ref "C15") (pin "1") (pinfunction "1_1") (pintype "passive"))
      (node (ref "IC1") (pin "4") (pinfunction "-IN_4") (pintype "input"))
      (node (ref "IC1") (pin "6") (pinfunction "-IN_6") (pintype "input"))
      (node (ref "R16") (pin "2") (pinfunction "2_2") (pintype "passive"))
    )
    (net (code "73") (name "Net-(IC1A-OUT)") (class "Default")
      (node (ref "IC1") (pin "1") (pinfunction "OUT_1") (pintype "open_collector"))
      (node (ref "IC1") (pin "13") (pinfunction "OUT_13") (pintype "open_collector"))
      (node (ref "IC1") (pin "14") (pinfunction "OUT_14") (pintype "open_collector"))
      (node (ref "IC1") (pin "2") (pinfunction "OUT_2") (pintype "open_collector"))
      (node (ref "IC2") (pin "1") (pinfunction "I0_1") (pintype "input"))
      (node (ref "R25") (pin "1") (pinfunction "1_1") (pintype "passive"))
    )
    (net (code "74") (name "Net-(IC1C-+IN)") (class "Default")
      (node (ref "C16") (pin "1") (pinfunction "1_1") (pintype "passive"))
      (node (ref "IC1") (pin "11") (pinfunction "+IN_11") (pintype "input"))
      (node (ref "IC1") (pin "9") (pinfunction "+IN_9") (pintype "input"))
      (node (ref "R17") (pin "2") (pinfunction "2_2") (pintype "passive"))
    )
    (net (code "75") (name "Net-(IC2A-I1)") (class "Default")
      (node (ref "IC2") (pin "2") (pinfunction "I1_2") (pintype "input"))
      (node (ref "IC2") (pin "6") (pinfunction "O_6") (pintype "output"))
    )
    (net (code "76") (name "Net-(IC2A-O)") (class "Default")
      (node (ref "IC2") (pin "3") (pinfunction "O_3") (pintype "output"))
      (node (ref "R19") (pin "2") (pinfunction "2_2") (pintype "passive"))
    )
    (net (code "77") (name "Net-(IC2B-I0)") (class "Default")
      (node (ref "IC2") (pin "4") (pinfunction "I0_4") (pintype "input"))
      (node (ref "IC2") (pin "5") (pinfunction "I1_5") (pintype "input"))
      (node (ref "IC2") (pin "8") (pinfunction "O_8") (pintype "output"))
    )
    (net (code "78") (name "Net-(IC5-OUT)") (class "Default")
      (node (ref "D1") (pin "C") (pinfunction "C_C") (pintype "passive"))
      (node (ref "IC5") (pin "2") (pinfunction "OUT_2") (pintype "output"))
      (node (ref "L1") (pin "1") (pinfunction "1_1") (pintype "passive"))
    )
    (net (code "79") (name "Net-(JP5-Pad2)") (class "Default")
      (node (ref "JP5") (pin "2") (pinfunction "2_2") (pintype "passive"))
      (node (ref "R2") (pin "1") (pinfunction "1_1") (pintype "passive"))
    )
    (net (code "80") (name "Net-(JP5-Pad3)") (class "Default")
      (node (ref "JP5") (pin "3") (pinfunction "3_3") (pintype "passive"))
      (node (ref "R1") (pin "2") (pinfunction "2_2") (pintype "passive"))
      (node (ref "T1") (pin "B") (pinfunction "B_B") (pintype "passive"))
    )
    (net (code "81") (name "Net-(JP5-Pad6)") (class "Default")
      (node (ref "JP5") (pin "6") (pinfunction "6_6") (pintype "passive"))
      (node (ref "R18") (pin "1") (pinfunction "1_1") (pintype "passive"))
      (node (ref "R22") (pin "2") (pinfunction "2_2") (pintype "passive"))
    )
    (net (code "82") (name "Net-(JP5-Pad8)") (class "Default")
      (node (ref "JP5") (pin "8") (pinfunction "8_8") (pintype "passive"))
      (node (ref "R23") (pin "2") (pinfunction "2_2") (pintype "passive"))
      (node (ref "R26") (pin "1") (pinfunction "1_1") (pintype "passive"))
    )
    (net (code "83") (name "Net-(R3-Pad1)") (class "Default")
      (node (ref "R3") (pin "1") (pinfunction "1_1") (pintype "passive"))
      (node (ref "R4") (pin "1") (pinfunction "1_1") (pintype "passive"))
      (node (ref "T1") (pin "C") (pinfunction "C_C") (pintype "passive"))
    )
    (net (code "84") (name "Net-(RN3-Pad2)") (class "Default")
      (node (ref "RN3") (pin "2") (pinfunction "2_2") (pintype "passive"))
      (node (ref "T2") (pin "B") (pinfunction "B_B") (pintype "passive"))
    )
    (net (code "85") (name "Net-(RN3B-2)") (class "Default")
      (node (ref "RN3") (pin "4") (pinfunction "2_4") (pintype "passive"))
      (node (ref "T3") (pin "B") (pinfunction "B_B") (pintype "passive"))
    )
    (net (code "86") (name "Net-(RN3C-2)") (class "Default")
      (node (ref "RN3") (pin "6") (pinfunction "2_6") (pintype "passive"))
      (node (ref "T4") (pin "B") (pinfunction "B_B") (pintype "passive"))
    )
    (net (code "87") (name "Net-(RN3D-2)") (class "Default")
      (node (ref "RN3") (pin "8") (pinfunction "2_8") (pintype "passive"))
      (node (ref "T5") (pin "B") (pinfunction "B_B") (pintype "passive"))
    )
    (net (code "88") (name "Net-(T6-B)") (class "Default")
      (node (ref "R9") (pin "2") (pinfunction "2_2") (pintype "passive"))
      (node (ref "T6") (pin "2") (pinfunction "B_2") (pintype "passive"))
    )
    (net (code "89") (name "unconnected-(IC2D-O-Pad11)") (class "Default")
      (node (ref "IC2") (pin "11") (pinfunction "O_11") (pintype "output"))
    )
    (net (code "90") (name "unconnected-(JP3-Pad13)") (class "Default")
      (node (ref "JP3") (pin "13") (pinfunction "13_13") (pintype "passive"))
    )
    (net (code "91") (name "unconnected-(JP3-Pad14)") (class "Default")
      (node (ref "JP3") (pin "14") (pinfunction "14_14") (pintype "passive"))
    )
    (net (code "92") (name "unconnected-(JP4-Pad14)") (class "Default")
      (node (ref "JP4") (pin "14") (pinfunction "14_14") (pintype "passive"))
    )
    (net (code "93") (name "unconnected-(JP4-Pad15)") (class "Default")
      (node (ref "JP4") (pin "15") (pinfunction "15_15") (pintype "passive"))
    )
    (net (code "94") (name "unconnected-(JP4-Pad16)") (class "Default")
      (node (ref "JP4") (pin "16") (pinfunction "16_16") (pintype "passive"))
    )
  )
)
